# TankBoardSheet2.net
KiCad netlist of a schematic drawn in Altium Designer
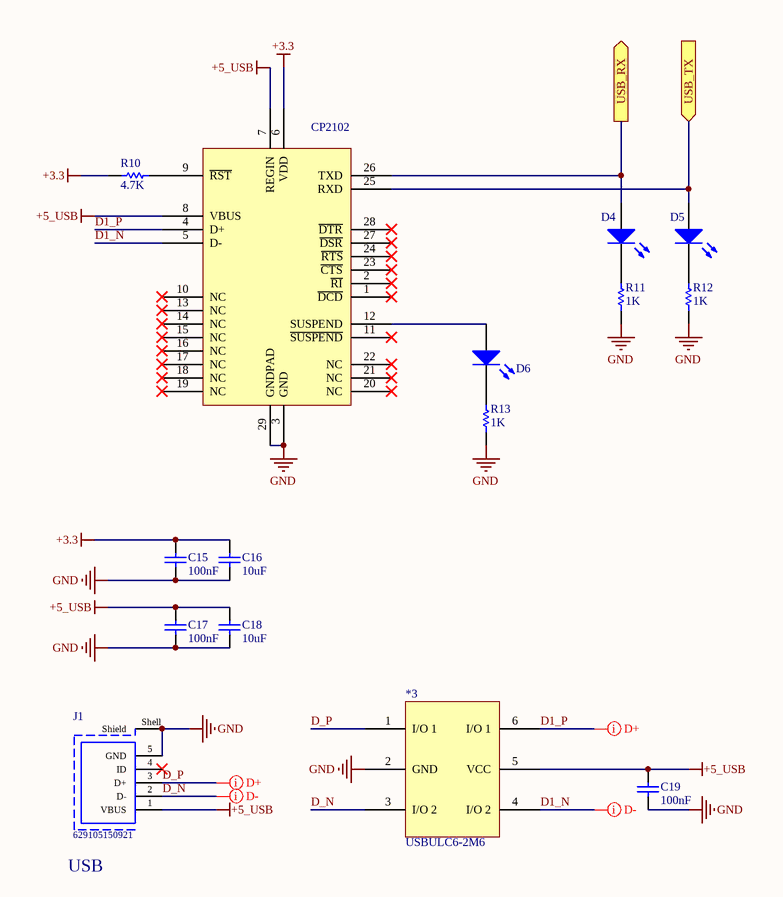
[diagram p0: TankBoardSheet2.SchDoc]

(export (version "E")
  (design (tool "Eeschema 10.0.6"))
  (components
    (comp (ref "*2")
      (value "CP2102")
      (footprint "QFN50P500X500X90_HS-29N")
      (libsource (lib "MiclsLib") (part "CP2102"))
    )
    (comp (ref "*3")
      (value "USBULC6-2M6")
      (footprint "QFN50P100X145X60-6N")
      (libsource (lib "MiclsLib") (part "USBULC6-2M6"))
    )
    (comp (ref "C15")
      (value "100nF")
      (footprint "CAP-SM-0603")
      (description "Capacitor")
      (fields (field (name "Comment") "Cap Non-Pol SMD"))
      (libsource (lib "PIF_Library") (part "Cap Non-Pol SMD"))
    )
    (comp (ref "C16")
      (value "10uF")
      (footprint "CAP-SM-0603")
      (description "Capacitor")
      (fields (field (name "Comment") "Cap Non-Pol SMD"))
      (libsource (lib "PIF_Library") (part "Cap Non-Pol SMD"))
    )
    (comp (ref "C17")
      (value "100nF")
      (footprint "CAP-SM-0603")
      (description "Capacitor")
      (fields (field (name "Comment") "Cap Non-Pol SMD"))
      (libsource (lib "PIF_Library") (part "Cap Non-Pol SMD"))
    )
    (comp (ref "C18")
      (value "10uF")
      (footprint "CAP-SM-0603")
      (description "Capacitor")
      (fields (field (name "Comment") "Cap Non-Pol SMD"))
      (libsource (lib "PIF_Library") (part "Cap Non-Pol SMD"))
    )
    (comp (ref "C19")
      (value "100nF")
      (footprint "CAP-SM-0603")
      (description "Capacitor")
      (fields (field (name "Comment") "Cap Non-Pol SMD"))
      (libsource (lib "PIF_Library") (part "Cap Non-Pol SMD"))
    )
    (comp (ref "D4")
      (value "LED SMD")
      (footprint "LED_0603_Blue")
      (description "LED")
      (libsource (lib "PIF_Library") (part "LED SMD"))
    )
    (comp (ref "D5")
      (value "LED SMD")
      (footprint "LED_0603_Blue")
      (description "LED")
      (libsource (lib "PIF_Library") (part "LED SMD"))
    )
    (comp (ref "D6")
      (value "LED SMD")
      (footprint "LED_0603_Blue")
      (description "LED")
      (libsource (lib "PIF_Library") (part "LED SMD"))
    )
    (comp (ref "J1")
      (value "629105150921")
      (footprint "629105150921")
      (description "Micro USB 2.0 Type AB Receptacle WR-COM, Horizontal, SMT")
      (fields (field (name "PUBLISHER") "Wurth Elektronik"))
      (libsource (lib "ALTIUM-WR-COM_USB_20-rev18d") (part "629105150921"))
    )
    (comp (ref "R10")
      (value "4.7K")
      (footprint "RES-SM-0603")
      (description "Resistor")
      (fields (field (name "Comment") "RESISTOR SMD"))
      (libsource (lib "PIF_Library") (part "RESISTOR SMD"))
    )
    (comp (ref "R11")
      (value "1K")
      (footprint "RES-SM-0603")
      (description "Resistor")
      (fields (field (name "Comment") "RESISTOR SMD"))
      (libsource (lib "PIF_Library") (part "RESISTOR SMD"))
    )
    (comp (ref "R12")
      (value "1K")
      (footprint "RES-SM-0603")
      (description "Resistor")
      (fields (field (name "Comment") "RESISTOR SMD"))
      (libsource (lib "PIF_Library") (part "RESISTOR SMD"))
    )
    (comp (ref "R13")
      (value "1K")
      (footprint "RES-SM-0603")
      (description "Resistor")
      (fields (field (name "Comment") "RESISTOR SMD"))
      (libsource (lib "PIF_Library") (part "RESISTOR SMD"))
    )
  )
  (nets
    (net (code "1") (name "+3.3") (class "Default")
      (node (ref "*2") (pin "6") (pinfunction "VDD_6") (pintype "passive"))
      (node (ref "C15") (pin "1") (pinfunction "1_1") (pintype "passive"))
      (node (ref "C16") (pin "1") (pinfunction "1_1") (pintype "passive"))
      (node (ref "R10") (pin "2") (pinfunction "2_2") (pintype "passive"))
    )
    (net (code "2") (name "+5_USB") (class "Default")
      (node (ref "*2") (pin "7") (pinfunction "REGIN_7") (pintype "passive"))
      (node (ref "*2") (pin "8") (pinfunction "VBUS_8") (pintype "passive"))
      (node (ref "*3") (pin "5") (pinfunction "VCC_5") (pintype "passive"))
      (node (ref "C17") (pin "1") (pinfunction "1_1") (pintype "passive"))
      (node (ref "C18") (pin "1") (pinfunction "1_1") (pintype "passive"))
      (node (ref "C19") (pin "1") (pinfunction "1_1") (pintype "passive"))
      (node (ref "J1") (pin "1") (pinfunction "VBUS_1") (pintype "passive"))
    )
    (net (code "3") (name "/D1_N") (class "Default")
      (node (ref "*2") (pin "5") (pinfunction "D-_5") (pintype "passive"))
      (node (ref "*3") (pin "4") (pinfunction "I/O_2_4") (pintype "passive"))
    )
    (net (code "4") (name "/D1_P") (class "Default")
      (node (ref "*2") (pin "4") (pinfunction "D+_4") (pintype "passive"))
      (node (ref "*3") (pin "6") (pinfunction "I/O_1_6") (pintype "passive"))
    )
    (net (code "5") (name "/D_N") (class "Default")
      (node (ref "*3") (pin "3") (pinfunction "I/O_2_3") (pintype "passive"))
      (node (ref "J1") (pin "2") (pinfunction "D-_2") (pintype "passive"))
    )
    (net (code "6") (name "/D_P") (class "Default")
      (node (ref "*3") (pin "1") (pinfunction "I/O_1_1") (pintype "passive"))
      (node (ref "J1") (pin "3") (pinfunction "D+_3") (pintype "passive"))
    )
    (net (code "7") (name "/USB_RX") (class "Default")
      (node (ref "*2") (pin "26") (pinfunction "TXD_26") (pintype "passive"))
      (node (ref "D4") (pin "1") (pinfunction "A_1") (pintype "passive"))
    )
    (net (code "8") (name "/USB_TX") (class "Default")
      (node (ref "*2") (pin "25") (pinfunction "RXD_25") (pintype "passive"))
      (node (ref "D5") (pin "1") (pinfunction "A_1") (pintype "passive"))
    )
    (net (code "9") (name "GND") (class "Default")
      (node (ref "*2") (pin "29") (pinfunction "GNDPAD_29") (pintype "passive"))
      (node (ref "*2") (pin "3") (pinfunction "GND_3") (pintype "passive"))
      (node (ref "*3") (pin "2") (pinfunction "GND_2") (pintype "passive"))
      (node (ref "C15") (pin "2") (pinfunction "2_2") (pintype "passive"))
      (node (ref "C16") (pin "2") (pinfunction "2_2") (pintype "passive"))
      (node (ref "C17") (pin "2") (pinfunction "2_2") (pintype "passive"))
      (node (ref "C18") (pin "2") (pinfunction "2_2") (pintype "passive"))
      (node (ref "C19") (pin "2") (pinfunction "2_2") (pintype "passive"))
      (node (ref "J1") (pin "5") (pinfunction "GND_5") (pintype "passive"))
      (node (ref "J1") (pin "Shell") (pinfunction "Shield_Shell") (pintype "passive"))
      (node (ref "R11") (pin "1") (pinfunction "1_1") (pintype "passive"))
      (node (ref "R12") (pin "1") (pinfunction "1_1") (pintype "passive"))
      (node (ref "R13") (pin "1") (pinfunction "1_1") (pintype "passive"))
    )
    (net (code "10") (name "Net-(*2-SUSPEND)") (class "Default")
      (node (ref "*2") (pin "12") (pinfunction "SUSPEND_12") (pintype "passive"))
      (node (ref "D6") (pin "1") (pinfunction "A_1") (pintype "passive"))
    )
    (net (code "11") (name "Net-(*2-~{RST})") (class "Default")
      (node (ref "*2") (pin "9") (pinfunction "~{RST}_9") (pintype "passive"))
      (node (ref "R10") (pin "1") (pinfunction "1_1") (pintype "passive"))
    )
    (net (code "12") (name "Net-(D4-K)") (class "Default")
      (node (ref "D4") (pin "2") (pinfunction "K_2") (pintype "passive"))
      (node (ref "R11") (pin "2") (pinfunction "2_2") (pintype "passive"))
    )
    (net (code "13") (name "Net-(D5-K)") (class "Default")
      (node (ref "D5") (pin "2") (pinfunction "K_2") (pintype "passive"))
      (node (ref "R12") (pin "2") (pinfunction "2_2") (pintype "passive"))
    )
    (net (code "14") (name "Net-(D6-K)") (class "Default")
      (node (ref "D6") (pin "2") (pinfunction "K_2") (pintype "passive"))
      (node (ref "R13") (pin "2") (pinfunction "2_2") (pintype "passive"))
    )
    (net (code "15") (name "unconnected-(*2-NC-Pad10)") (class "Default")
      (node (ref "*2") (pin "10") (pinfunction "NC_10") (pintype "passive+no_connect"))
    )
    (net (code "16") (name "unconnected-(*2-NC-Pad13)") (class "Default")
      (node (ref "*2") (pin "13") (pinfunction "NC_13") (pintype "passive+no_connect"))
    )
    (net (code "17") (name "unconnected-(*2-NC-Pad14)") (class "Default")
      (node (ref "*2") (pin "14") (pinfunction "NC_14") (pintype "passive+no_connect"))
    )
    (net (code "18") (name "unconnected-(*2-NC-Pad15)") (class "Default")
      (node (ref "*2") (pin "15") (pinfunction "NC_15") (pintype "passive+no_connect"))
    )
    (net (code "19") (name "unconnected-(*2-NC-Pad16)") (class "Default")
      (node (ref "*2") (pin "16") (pinfunction "NC_16") (pintype "passive+no_connect"))
    )
    (net (code "20") (name "unconnected-(*2-NC-Pad17)") (class "Default")
      (node (ref "*2") (pin "17") (pinfunction "NC_17") (pintype "passive+no_connect"))
    )
    (net (code "21") (name "unconnected-(*2-NC-Pad18)") (class "Default")
      (node (ref "*2") (pin "18") (pinfunction "NC_18") (pintype "passive+no_connect"))
    )
    (net (code "22") (name "unconnected-(*2-NC-Pad19)") (class "Default")
      (node (ref "*2") (pin "19") (pinfunction "NC_19") (pintype "passive+no_connect"))
    )
    (net (code "23") (name "unconnected-(*2-NC-Pad20)") (class "Default")
      (node (ref "*2") (pin "20") (pinfunction "NC_20") (pintype "passive+no_connect"))
    )
    (net (code "24") (name "unconnected-(*2-NC-Pad21)") (class "Default")
      (node (ref "*2") (pin "21") (pinfunction "NC_21") (pintype "passive+no_connect"))
    )
    (net (code "25") (name "unconnected-(*2-NC-Pad22)") (class "Default")
      (node (ref "*2") (pin "22") (pinfunction "NC_22") (pintype "passive+no_connect"))
    )
    (net (code "26") (name "unconnected-(*2-~{CTS}-Pad23)") (class "Default")
      (node (ref "*2") (pin "23") (pinfunction "~{CTS}_23") (pintype "passive+no_connect"))
    )
    (net (code "27") (name "unconnected-(*2-~{DCD}-Pad1)") (class "Default")
      (node (ref "*2") (pin "1") (pinfunction "~{DCD}_1") (pintype "passive+no_connect"))
    )
    (net (code "28") (name "unconnected-(*2-~{DSR}-Pad27)") (class "Default")
      (node (ref "*2") (pin "27") (pinfunction "~{DSR}_27") (pintype "passive+no_connect"))
    )
    (net (code "29") (name "unconnected-(*2-~{DTR}-Pad28)") (class "Default")
      (node (ref "*2") (pin "28") (pinfunction "~{DTR}_28") (pintype "passive+no_connect"))
    )
    (net (code "30") (name "unconnected-(*2-~{RI}-Pad2)") (class "Default")
      (node (ref "*2") (pin "2") (pinfunction "~{RI}_2") (pintype "passive+no_connect"))
    )
    (net (code "31") (name "unconnected-(*2-~{RTS}-Pad24)") (class "Default")
      (node (ref "*2") (pin "24") (pinfunction "~{RTS}_24") (pintype "passive+no_connect"))
    )
    (net (code "32") (name "unconnected-(*2-~{SUSPEND}-Pad11)") (class "Default")
      (node (ref "*2") (pin "11") (pinfunction "~{SUSPEND}_11") (pintype "passive+no_connect"))
    )
    (net (code "33") (name "unconnected-(J1-ID-Pad4)") (class "Default")
      (node (ref "J1") (pin "4") (pinfunction "ID_4") (pintype "passive+no_connect"))
    )
  )
)
